# CON_MEZZANINE_ADC.net
KiCad netlist of a schematic drawn in Altium Designer
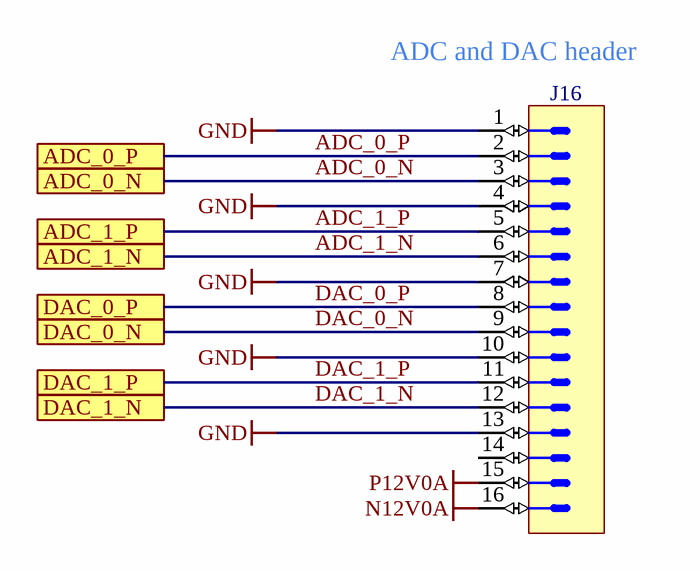
[diagram p0: CON_MEZZANINE_ADC.SchDoc]

(export (version "E")
  (design (tool "Eeschema 10.0.6"))
  (components
    (comp (ref "J16")
      (value "Header 16")
      (footprint "3M_N2516-6002RB")
      (description "Connector 16 Male")
      (fields
        (field (name "PART NUMBER") "3M_N2516-6002RB")
        (field (name "MANUFACTURER") "3M")
        (field (name "AUTHOR") "CERN DEM JLC")
      )
      (libsource (lib "Connectors") (part "Connector 16 Male"))
    )
  )
  (nets
    (net (code "1") (name "/ADC_0_N") (class "Default")
      (node (ref "J16") (pin "3") (pinfunction "3_3") (pintype "bidirectional"))
    )
    (net (code "2") (name "/ADC_0_P") (class "Default")
      (node (ref "J16") (pin "2") (pinfunction "2_2") (pintype "bidirectional"))
    )
    (net (code "3") (name "/ADC_1_N") (class "Default")
      (node (ref "J16") (pin "6") (pinfunction "6_6") (pintype "bidirectional"))
    )
    (net (code "4") (name "/ADC_1_P") (class "Default")
      (node (ref "J16") (pin "5") (pinfunction "5_5") (pintype "bidirectional"))
    )
    (net (code "5") (name "/DAC_0_N") (class "Default")
      (node (ref "J16") (pin "9") (pinfunction "9_9") (pintype "bidirectional"))
    )
    (net (code "6") (name "/DAC_0_P") (class "Default")
      (node (ref "J16") (pin "8") (pinfunction "8_8") (pintype "bidirectional"))
    )
    (net (code "7") (name "/DAC_1_N") (class "Default")
      (node (ref "J16") (pin "12") (pinfunction "12_12") (pintype "bidirectional"))
    )
    (net (code "8") (name "/DAC_1_P") (class "Default")
      (node (ref "J16") (pin "11") (pinfunction "11_11") (pintype "bidirectional"))
    )
    (net (code "9") (name "GND") (class "Default")
      (node (ref "J16") (pin "1") (pinfunction "1_1") (pintype "bidirectional"))
      (node (ref "J16") (pin "10") (pinfunction "10_10") (pintype "bidirectional"))
      (node (ref "J16") (pin "13") (pinfunction "13_13") (pintype "bidirectional"))
      (node (ref "J16") (pin "4") (pinfunction "4_4") (pintype "bidirectional"))
      (node (ref "J16") (pin "7") (pinfunction "7_7") (pintype "bidirectional"))
    )
    (net (code "10") (name "N12V0A") (class "Default")
      (node (ref "J16") (pin "16") (pinfunction "16_16") (pintype "bidirectional"))
    )
    (net (code "11") (name "P12V0A") (class "Default")
      (node (ref "J16") (pin "15") (pinfunction "15_15") (pintype "bidirectional"))
    )
    (net (code "12") (name "unconnected-(J16-Pad14)") (class "Default")
      (node (ref "J16") (pin "14") (pinfunction "14_14") (pintype "bidirectional"))
    )
  )
)
